# DAM10_Ethernet.net
KiCad netlist of a schematic drawn in Altium Designer
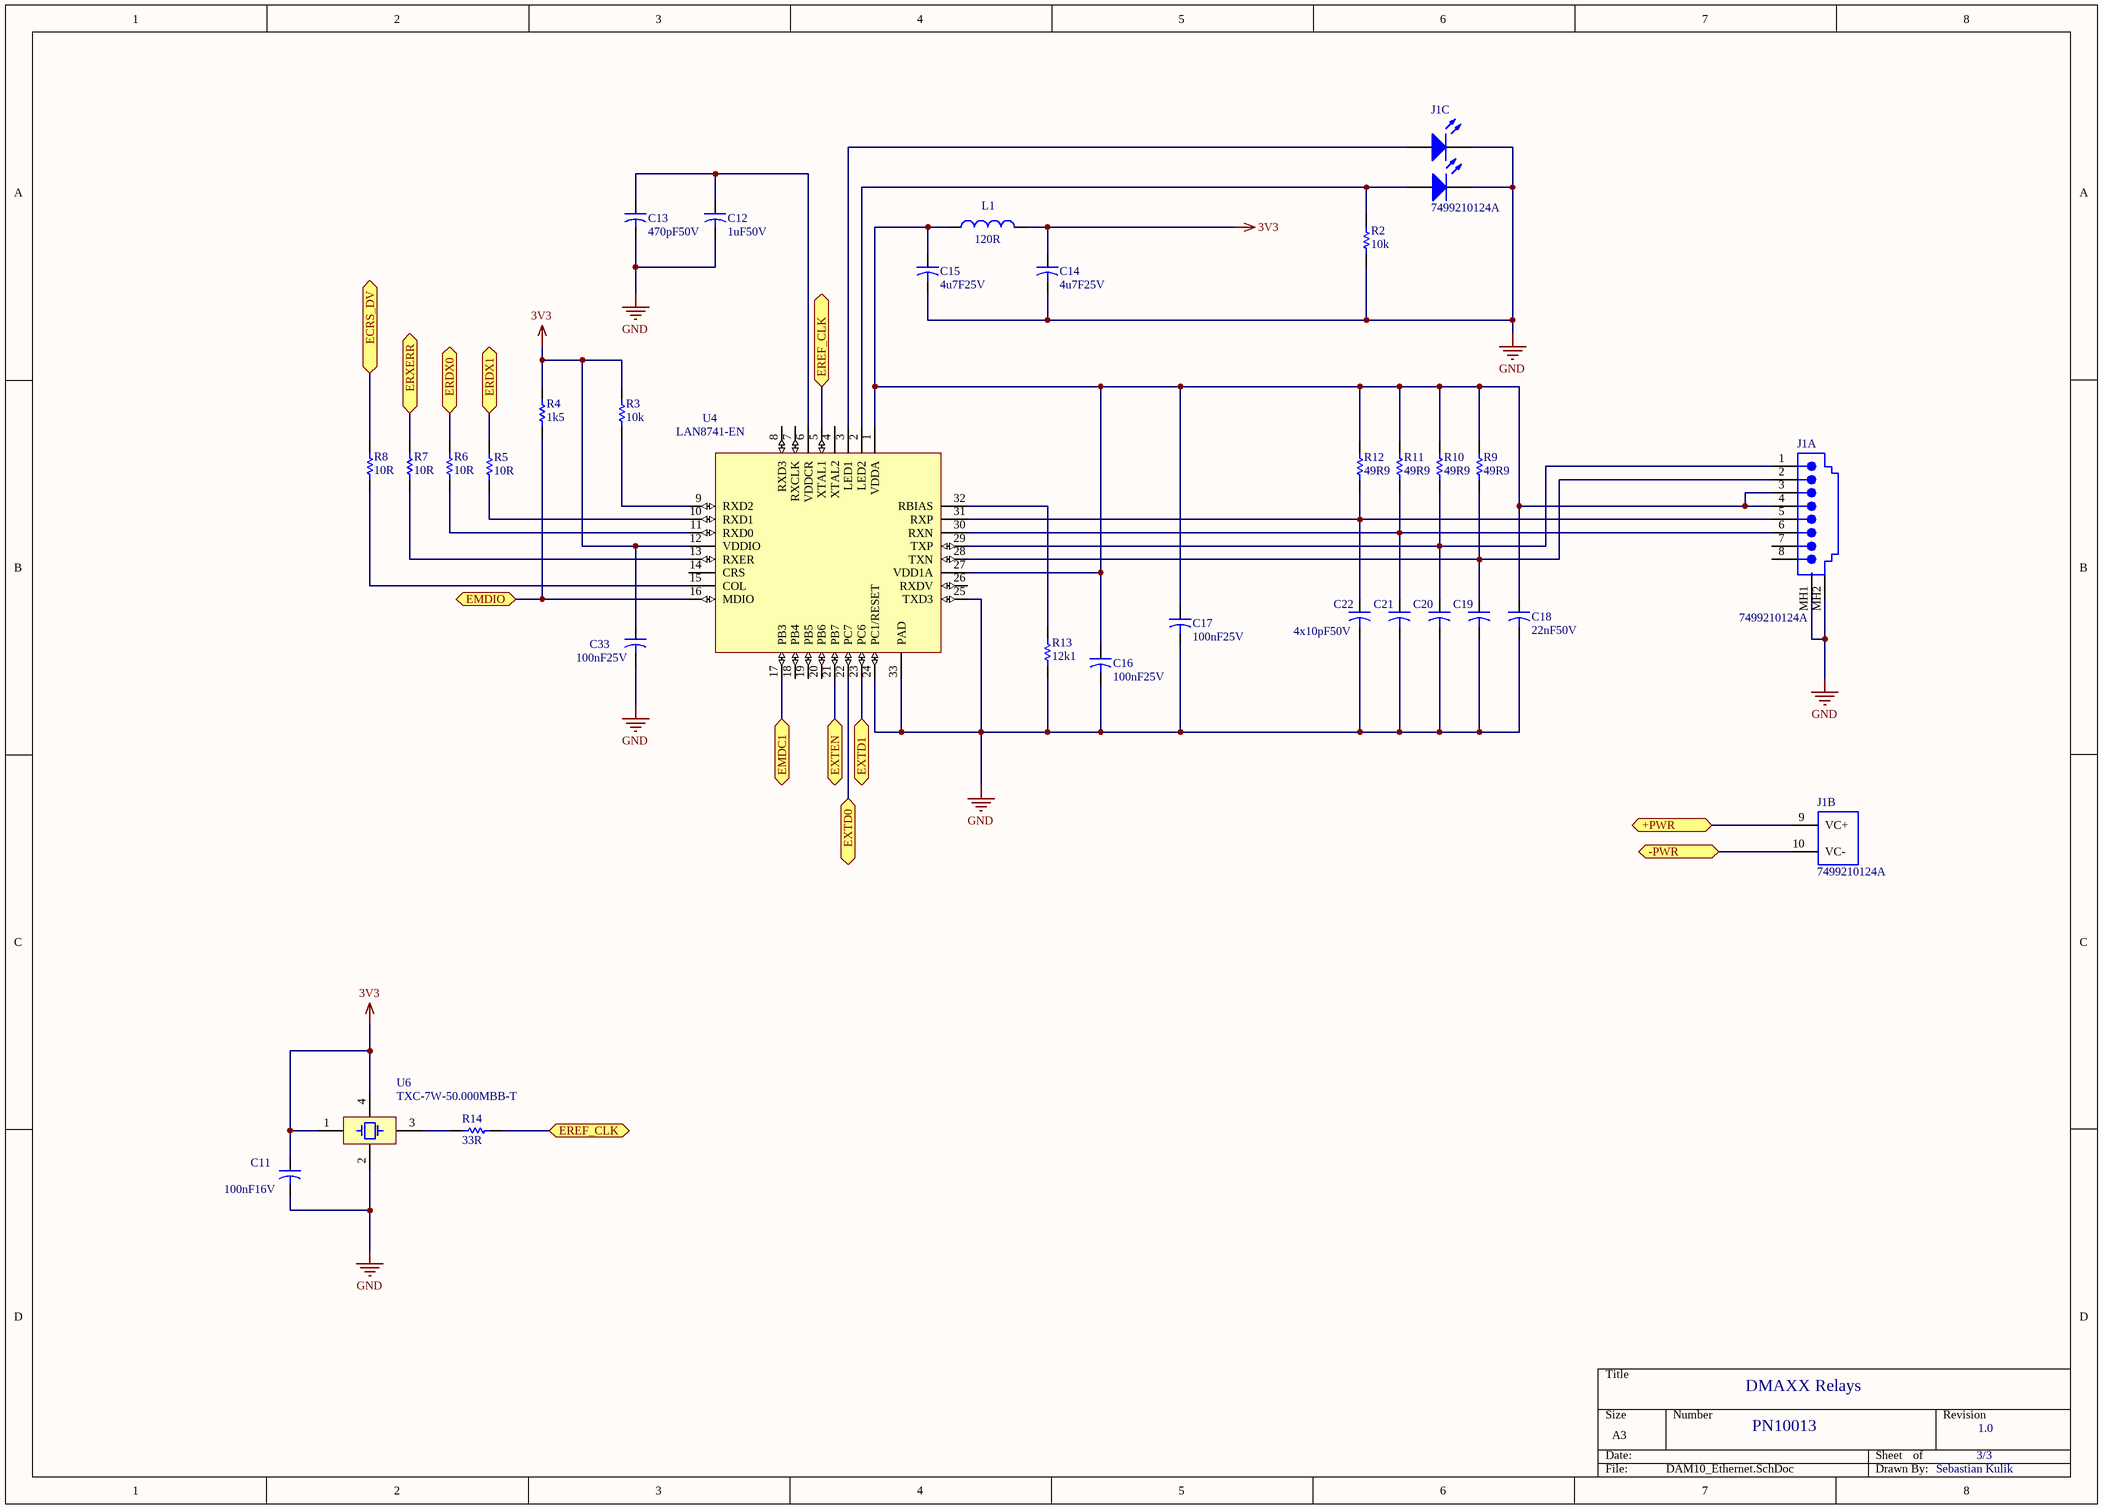
[diagram p0: DAM10_Ethernet.SchDoc]

(export (version "E")
  (design (tool "Eeschema 10.0.6"))
  (components
    (comp (ref "C11")
      (value "100nF16V")
      (footprint "C0402")
      (description "Capacitor")
      (fields
        (field (name "MANUFACTURER") "TDK")
        (field (name "Comment") "100nF16V_0402")
        (field (name "PUBLISHER") "Sebastian Kulik")
      )
      (libsource (lib "Capacitors") (part "100nF16V_0402"))
    )
    (comp (ref "C12")
      (value "1uF50V")
      (footprint "C0603")
      (description "C series, X5R, 10%")
      (fields
        (field (name "MANUFACTURER") "TDK")
        (field (name "Comment") "1uF50V_0603")
        (field (name "PUBLISHER") "Sebastian Kulik")
      )
      (libsource (lib "Capacitors") (part "1uF50V_0603"))
    )
    (comp (ref "C13")
      (value "470pF50V")
      (footprint "C0402")
      (description "AVX, 50V")
      (fields
        (field (name "MANUFACTURER") "AVX")
        (field (name "Comment") "470pF50V_0402")
        (field (name "PUBLISHER") "Sebastian Kulik")
      )
      (libsource (lib "Capacitors") (part "470pF50V_0402"))
    )
    (comp (ref "C14")
      (value "4u7F25V")
      (footprint "C0805")
      (description "TDK  C series, X7R, 10%, 25V")
      (fields
        (field (name "MANUFACTURER") "TDK")
        (field (name "Comment") "4u7F25V_0805")
        (field (name "PUBLISHER") "Sebastian Kulik")
      )
      (libsource (lib "Capacitors") (part "4u7F25V_0805"))
    )
    (comp (ref "C15")
      (value "4u7F25V")
      (footprint "C0805")
      (description "TDK  C series, X7R, 10%, 25V")
      (fields
        (field (name "MANUFACTURER") "TDK")
        (field (name "Comment") "4u7F25V_0805")
        (field (name "PUBLISHER") "Sebastian Kulik")
      )
      (libsource (lib "Capacitors") (part "4u7F25V_0805"))
    )
    (comp (ref "C16")
      (value "100nF25V")
      (footprint "C0402")
      (description "AVX, X5R, 10%, 25V")
      (fields
        (field (name "MANUFACTURER") "AVX")
        (field (name "Comment") "100nF25V_0402")
        (field (name "PUBLISHER") "Sebastian Kulik")
      )
      (libsource (lib "Capacitors") (part "100nF25V_0402"))
    )
    (comp (ref "C17")
      (value "100nF25V")
      (footprint "C0402")
      (description "AVX, X5R, 10%, 25V")
      (fields
        (field (name "MANUFACTURER") "AVX")
        (field (name "Comment") "100nF25V_0402")
        (field (name "PUBLISHER") "Sebastian Kulik")
      )
      (libsource (lib "Capacitors") (part "100nF25V_0402"))
    )
    (comp (ref "C18")
      (value "22nF50V")
      (footprint "C0603")
      (description "AVX ,  X7R, 5%, 50V")
      (fields
        (field (name "MANUFACTURER") "AVX")
        (field (name "Comment") "22nF50V_0603")
        (field (name "PUBLISHER") "Sebastian Kulik")
      )
      (libsource (lib "Capacitors") (part "22nF50V_0603"))
    )
    (comp (ref "C19")
      (value "10pF50V_0603")
      (footprint "C0603")
      (description "AVX ,  +-0.5pF, 50V")
      (fields (field (name "MANUFACTURER") "AVX") (field (name "PUBLISHER") "Sebastian Kulik"))
      (libsource (lib "Capacitors") (part "10pF50V_0603"))
    )
    (comp (ref "C20")
      (value "10pF50V_0603")
      (footprint "C0603")
      (description "AVX ,  +-0.5pF, 50V")
      (fields (field (name "MANUFACTURER") "AVX") (field (name "PUBLISHER") "Sebastian Kulik"))
      (libsource (lib "Capacitors") (part "10pF50V_0603"))
    )
    (comp (ref "C21")
      (value "10pF50V_0603")
      (footprint "C0603")
      (description "AVX ,  +-0.5pF, 50V")
      (fields (field (name "MANUFACTURER") "AVX") (field (name "PUBLISHER") "Sebastian Kulik"))
      (libsource (lib "Capacitors") (part "10pF50V_0603"))
    )
    (comp (ref "C22")
      (value "10pF50V_0603")
      (footprint "C0603")
      (description "AVX ,  +-0.5pF, 50V")
      (fields (field (name "MANUFACTURER") "AVX") (field (name "PUBLISHER") "Sebastian Kulik"))
      (libsource (lib "Capacitors") (part "10pF50V_0603"))
    )
    (comp (ref "C33")
      (value "100nF25V")
      (footprint "C0402")
      (description "AVX, X5R, 10%, 25V")
      (fields
        (field (name "MANUFACTURER") "AVX")
        (field (name "Comment") "100nF25V_0402")
        (field (name "PUBLISHER") "Sebastian Kulik")
      )
      (libsource (lib "Capacitors") (part "100nF25V_0402"))
    )
    (comp (ref "J1")
      (value "7499210124A")
      (footprint "7499210124A")
      (description "Modular Jack , Right Angle RJ-45, Low Profile")
      (fields (field (name "MANUFACTURER") "Wuerth Elektronik") (field (name "PUBLISHER") "Sebastian Kulik"))
      (libsource (lib "Connectors") (part "Ethernet, POE, WE7499210124A"))
    )
    (comp (ref "L1")
      (value "120R")
      (footprint "L0603")
      (description "Murata, Ferrit, 120Rx2A")
      (fields
        (field (name "MANUFACTURER") "Murata")
        (field (name "Comment") "120R4A_0603")
        (field (name "PUBLISHER") "Sebastian Kulik")
      )
      (libsource (lib "Passives") (part "120R4A_0603"))
    )
    (comp (ref "R2")
      (value "10k")
      (footprint "R0402")
      (description "Vishay CRCW series, 125mW, 1%")
      (fields
        (field (name "MANUFACTURER") "Vishay")
        (field (name "Comment") "10k_0402")
        (field (name "PUBLISHER") "Sebastian Kulik")
      )
      (libsource (lib "Resistors") (part "10k_0402"))
    )
    (comp (ref "R3")
      (value "10k")
      (footprint "R0402")
      (description "Vishay CRCW series, 125mW, 1%")
      (fields
        (field (name "MANUFACTURER") "Vishay")
        (field (name "Comment") "10k_0402")
        (field (name "PUBLISHER") "Sebastian Kulik")
      )
      (libsource (lib "Resistors") (part "10k_0402"))
    )
    (comp (ref "R4")
      (value "1k5")
      (footprint "R0402")
      (description "Vishay CRCW series, 125mW, 1%")
      (fields
        (field (name "MANUFACTURER") "Vishay")
        (field (name "Comment") "1k5_0402")
        (field (name "PUBLISHER") "Sebastian Kulik")
      )
      (libsource (lib "Resistors") (part "1k5_0402"))
    )
    (comp (ref "R5")
      (value "10R")
      (footprint "R0402")
      (description "Vishay CRCW series, 125mW, 1%")
      (fields
        (field (name "MANUFACTURER") "Vishay")
        (field (name "Comment") "10R_0402")
        (field (name "PUBLISHER") "Sebastian Kulik")
      )
      (libsource (lib "Resistors") (part "10R_0402"))
    )
    (comp (ref "R6")
      (value "10R")
      (footprint "R0402")
      (description "Vishay CRCW series, 125mW, 1%")
      (fields
        (field (name "MANUFACTURER") "Vishay")
        (field (name "Comment") "10R_0402")
        (field (name "PUBLISHER") "Sebastian Kulik")
      )
      (libsource (lib "Resistors") (part "10R_0402"))
    )
    (comp (ref "R7")
      (value "10R")
      (footprint "R0402")
      (description "Vishay CRCW series, 125mW, 1%")
      (fields
        (field (name "MANUFACTURER") "Vishay")
        (field (name "Comment") "10R_0402")
        (field (name "PUBLISHER") "Sebastian Kulik")
      )
      (libsource (lib "Resistors") (part "10R_0402"))
    )
    (comp (ref "R8")
      (value "10R")
      (footprint "R0402")
      (description "Vishay CRCW series, 125mW, 1%")
      (fields
        (field (name "MANUFACTURER") "Vishay")
        (field (name "Comment") "10R_0402")
        (field (name "PUBLISHER") "Sebastian Kulik")
      )
      (libsource (lib "Resistors") (part "10R_0402"))
    )
    (comp (ref "R9")
      (value "49R9")
      (footprint "R0402")
      (description "Vishay CRCW series, 63mW, 1%")
      (fields
        (field (name "MANUFACTURER") "Vishay")
        (field (name "Comment") "49R9_0402")
        (field (name "PUBLISHER") "Sebastian Kulik")
      )
      (libsource (lib "Resistors") (part "49R9_0402"))
    )
    (comp (ref "R10")
      (value "49R9")
      (footprint "R0402")
      (description "Vishay CRCW series, 63mW, 1%")
      (fields
        (field (name "MANUFACTURER") "Vishay")
        (field (name "Comment") "49R9_0402")
        (field (name "PUBLISHER") "Sebastian Kulik")
      )
      (libsource (lib "Resistors") (part "49R9_0402"))
    )
    (comp (ref "R11")
      (value "49R9")
      (footprint "R0402")
      (description "Vishay CRCW series, 63mW, 1%")
      (fields
        (field (name "MANUFACTURER") "Vishay")
        (field (name "Comment") "49R9_0402")
        (field (name "PUBLISHER") "Sebastian Kulik")
      )
      (libsource (lib "Resistors") (part "49R9_0402"))
    )
    (comp (ref "R12")
      (value "49R9")
      (footprint "R0402")
      (description "Vishay CRCW series, 63mW, 1%")
      (fields
        (field (name "MANUFACTURER") "Vishay")
        (field (name "Comment") "49R9_0402")
        (field (name "PUBLISHER") "Sebastian Kulik")
      )
      (libsource (lib "Resistors") (part "49R9_0402"))
    )
    (comp (ref "R13")
      (value "12k1")
      (footprint "R0603(1608)")
      (description "Vishay, CRCW series, 100mW, 1%")
      (fields
        (field (name "MANUFACTURER") "Vishay")
        (field (name "Comment") "12k1_0603")
        (field (name "PUBLISHER") "Sebastian Kulik")
      )
      (libsource (lib "Resistors") (part "12k1_0603"))
    )
    (comp (ref "R14")
      (value "33R")
      (footprint "R0402")
      (description "Vishay CRCW series, 63mW, 1%")
      (fields
        (field (name "MANUFACTURER") "Vishay")
        (field (name "Comment") "33R_0402")
        (field (name "PUBLISHER") "Sebastian Kulik")
      )
      (libsource (lib "Resistors") (part "33R_0402"))
    )
    (comp (ref "U4")
      (value "LAN8741-EN")
      (footprint "32M1-A_M")
      (description "Ethernet Phy")
      (fields (field (name "MANUFACTURER") "Microchip") (field (name "PUBLISHER") "Sebastian Kulik"))
      (libsource (lib "ICs") (part "LAN8741-EN"))
    )
    (comp (ref "U6")
      (value "TXC-7W-50.000MBB-T")
      (footprint "TXC_7W")
      (description "Crystal")
      (fields (field (name "MANUFACTURER") "TXC") (field (name "PUBLISHER") "Sebastian Kulik"))
      (libsource (lib "ICs") (part "TXC-7W-50.000MBB-T"))
    )
  )
  (nets
    (net (code "1") (name "/+PWR") (class "Default")
      (node (ref "J1") (pin "9") (pinfunction "VC+_9") (pintype "passive"))
    )
    (net (code "2") (name "/-PWR") (class "Default")
      (node (ref "J1") (pin "10") (pinfunction "VC-_10") (pintype "passive"))
    )
    (net (code "3") (name "/ECRS_DV") (class "Default")
      (node (ref "R8") (pin "2") (pinfunction "2_2") (pintype "passive"))
    )
    (net (code "4") (name "/EMDC1") (class "Default")
      (node (ref "U4") (pin "17") (pinfunction "PB3_17") (pintype "bidirectional"))
    )
    (net (code "5") (name "/EMDIO") (class "Default")
      (node (ref "R4") (pin "1") (pinfunction "1_1") (pintype "passive"))
      (node (ref "U4") (pin "16") (pinfunction "MDIO_16") (pintype "bidirectional"))
    )
    (net (code "6") (name "/ERDX0") (class "Default")
      (node (ref "R6") (pin "2") (pinfunction "2_2") (pintype "passive"))
    )
    (net (code "7") (name "/ERDX1") (class "Default")
      (node (ref "R5") (pin "1") (pinfunction "1_1") (pintype "passive"))
    )
    (net (code "8") (name "/EREF_CLK") (class "Default")
      (node (ref "R14") (pin "2") (pinfunction "2_2") (pintype "passive"))
      (node (ref "U4") (pin "5") (pinfunction "XTAL1_5") (pintype "bidirectional"))
    )
    (net (code "9") (name "/ERXERR") (class "Default")
      (node (ref "R7") (pin "2") (pinfunction "2_2") (pintype "passive"))
    )
    (net (code "10") (name "/EXTD0") (class "Default")
      (node (ref "U4") (pin "22") (pinfunction "PC7_22") (pintype "bidirectional"))
    )
    (net (code "11") (name "/EXTD1") (class "Default")
      (node (ref "U4") (pin "23") (pinfunction "PC6_23") (pintype "bidirectional"))
    )
    (net (code "12") (name "/EXTEN") (class "Default")
      (node (ref "U4") (pin "21") (pinfunction "PB7_21") (pintype "bidirectional"))
    )
    (net (code "13") (name "3V3") (class "Default")
      (node (ref "C11") (pin "1") (pinfunction "1_1") (pintype "passive"))
      (node (ref "C14") (pin "1") (pinfunction "1_1") (pintype "passive"))
      (node (ref "C33") (pin "1") (pinfunction "1_1") (pintype "passive"))
      (node (ref "L1") (pin "2") (pinfunction "2_2") (pintype "passive"))
      (node (ref "R3") (pin "2") (pinfunction "2_2") (pintype "passive"))
      (node (ref "R4") (pin "2") (pinfunction "2_2") (pintype "passive"))
      (node (ref "U4") (pin "12") (pinfunction "VDDIO_12") (pintype "passive"))
      (node (ref "U6") (pin "1") (pinfunction "E/D_1") (pintype "passive"))
      (node (ref "U6") (pin "4") (pinfunction "VCC_4") (pintype "passive"))
    )
    (net (code "14") (name "GND") (class "Default")
      (node (ref "C11") (pin "2") (pinfunction "2_2") (pintype "passive"))
      (node (ref "C12") (pin "2") (pinfunction "2_2") (pintype "passive"))
      (node (ref "C13") (pin "2") (pinfunction "2_2") (pintype "passive"))
      (node (ref "C14") (pin "2") (pinfunction "2_2") (pintype "passive"))
      (node (ref "C15") (pin "2") (pinfunction "2_2") (pintype "passive"))
      (node (ref "C16") (pin "2") (pinfunction "2_2") (pintype "passive"))
      (node (ref "C17") (pin "2") (pinfunction "2_2") (pintype "passive"))
      (node (ref "C18") (pin "2") (pinfunction "2_2") (pintype "passive"))
      (node (ref "C19") (pin "2") (pinfunction "2_2") (pintype "passive"))
      (node (ref "C20") (pin "2") (pinfunction "2_2") (pintype "passive"))
      (node (ref "C21") (pin "2") (pinfunction "2_2") (pintype "passive"))
      (node (ref "C22") (pin "2") (pinfunction "2_2") (pintype "passive"))
      (node (ref "C33") (pin "2") (pinfunction "2_2") (pintype "passive"))
      (node (ref "J1") (pin "11") (pinfunction "K_11") (pintype "passive"))
      (node (ref "J1") (pin "13") (pinfunction "K_13") (pintype "passive"))
      (node (ref "J1") (pin "MH1") (pinfunction "Shield_MH1") (pintype "passive"))
      (node (ref "J1") (pin "MH2") (pinfunction "Shield_MH2") (pintype "passive"))
      (node (ref "R13") (pin "1") (pinfunction "1_1") (pintype "passive"))
      (node (ref "R2") (pin "1") (pinfunction "1_1") (pintype "passive"))
      (node (ref "U4") (pin "24") (pinfunction "PC1/RESET_24") (pintype "bidirectional"))
      (node (ref "U4") (pin "25") (pinfunction "TXD3_25") (pintype "bidirectional"))
      (node (ref "U4") (pin "33") (pinfunction "PAD_33") (pintype "power_in"))
      (node (ref "U6") (pin "2") (pinfunction "GND_2") (pintype "passive"))
    )
    (net (code "15") (name "Net-(U4-COL)") (class "Default")
      (node (ref "R8") (pin "1") (pinfunction "1_1") (pintype "passive"))
      (node (ref "U4") (pin "15") (pinfunction "COL_15") (pintype "passive"))
    )
    (net (code "16") (name "Net-(U4-LED1)") (class "Default")
      (node (ref "J1") (pin "12") (pinfunction "A_12") (pintype "passive"))
      (node (ref "U4") (pin "3") (pinfunction "LED1_3") (pintype "power_in"))
    )
    (net (code "17") (name "Net-(U4-LED2)") (class "Default")
      (node (ref "J1") (pin "14") (pinfunction "A_14") (pintype "passive"))
      (node (ref "R2") (pin "2") (pinfunction "2_2") (pintype "passive"))
      (node (ref "U4") (pin "2") (pinfunction "LED2_2") (pintype "passive"))
    )
    (net (code "18") (name "Net-(U4-RBIAS)") (class "Default")
      (node (ref "R13") (pin "2") (pinfunction "2_2") (pintype "passive"))
      (node (ref "U4") (pin "32") (pinfunction "RBIAS_32") (pintype "power_in"))
    )
    (net (code "19") (name "Net-(U4-RXD0)") (class "Default")
      (node (ref "R6") (pin "1") (pinfunction "1_1") (pintype "passive"))
      (node (ref "U4") (pin "11") (pinfunction "RXD0_11") (pintype "bidirectional"))
    )
    (net (code "20") (name "Net-(U4-RXD1)") (class "Default")
      (node (ref "R5") (pin "2") (pinfunction "2_2") (pintype "passive"))
      (node (ref "U4") (pin "10") (pinfunction "RXD1_10") (pintype "bidirectional"))
    )
    (net (code "21") (name "Net-(U4-RXD2)") (class "Default")
      (node (ref "R3") (pin "1") (pinfunction "1_1") (pintype "passive"))
      (node (ref "U4") (pin "9") (pinfunction "RXD2_9") (pintype "bidirectional"))
    )
    (net (code "22") (name "Net-(U4-RXER)") (class "Default")
      (node (ref "R7") (pin "1") (pinfunction "1_1") (pintype "passive"))
      (node (ref "U4") (pin "13") (pinfunction "RXER_13") (pintype "bidirectional"))
    )
    (net (code "23") (name "Net-(U4-RXN)") (class "Default")
      (node (ref "C21") (pin "1") (pinfunction "1_1") (pintype "passive"))
      (node (ref "J1") (pin "6") (pinfunction "6_6") (pintype "passive"))
      (node (ref "R11") (pin "1") (pinfunction "1_1") (pintype "passive"))
      (node (ref "U4") (pin "30") (pinfunction "RXN_30") (pintype "passive"))
    )
    (net (code "24") (name "Net-(U4-RXP)") (class "Default")
      (node (ref "C22") (pin "1") (pinfunction "1_1") (pintype "passive"))
      (node (ref "J1") (pin "5") (pinfunction "5_5") (pintype "passive"))
      (node (ref "R12") (pin "1") (pinfunction "1_1") (pintype "passive"))
      (node (ref "U4") (pin "31") (pinfunction "RXP_31") (pintype "passive"))
    )
    (net (code "25") (name "Net-(U4-TXN)") (class "Default")
      (node (ref "C19") (pin "1") (pinfunction "1_1") (pintype "passive"))
      (node (ref "J1") (pin "2") (pinfunction "2_2") (pintype "passive"))
      (node (ref "R9") (pin "1") (pinfunction "1_1") (pintype "passive"))
      (node (ref "U4") (pin "28") (pinfunction "TXN_28") (pintype "bidirectional"))
    )
    (net (code "26") (name "Net-(U4-TXP)") (class "Default")
      (node (ref "C20") (pin "1") (pinfunction "1_1") (pintype "passive"))
      (node (ref "J1") (pin "1") (pinfunction "1_1") (pintype "passive"))
      (node (ref "R10") (pin "1") (pinfunction "1_1") (pintype "passive"))
      (node (ref "U4") (pin "29") (pinfunction "TXP_29") (pintype "bidirectional"))
    )
    (net (code "27") (name "Net-(U4-VDD1A)") (class "Default")
      (node (ref "C15") (pin "1") (pinfunction "1_1") (pintype "passive"))
      (node (ref "C16") (pin "1") (pinfunction "1_1") (pintype "passive"))
      (node (ref "C17") (pin "1") (pinfunction "1_1") (pintype "passive"))
      (node (ref "C18") (pin "1") (pinfunction "1_1") (pintype "passive"))
      (node (ref "J1") (pin "3") (pinfunction "3_3") (pintype "passive"))
      (node (ref "J1") (pin "4") (pinfunction "4_4") (pintype "passive"))
      (node (ref "L1") (pin "1") (pinfunction "1_1") (pintype "passive"))
      (node (ref "R10") (pin "2") (pinfunction "2_2") (pintype "passive"))
      (node (ref "R11") (pin "2") (pinfunction "2_2") (pintype "passive"))
      (node (ref "R12") (pin "2") (pinfunction "2_2") (pintype "passive"))
      (node (ref "R9") (pin "2") (pinfunction "2_2") (pintype "passive"))
      (node (ref "U4") (pin "1") (pinfunction "VDDA_1") (pintype "passive"))
      (node (ref "U4") (pin "27") (pinfunction "VDD1A_27") (pintype "passive"))
    )
    (net (code "28") (name "Net-(U4-VDDCR)") (class "Default")
      (node (ref "C12") (pin "1") (pinfunction "1_1") (pintype "passive"))
      (node (ref "C13") (pin "1") (pinfunction "1_1") (pintype "passive"))
      (node (ref "U4") (pin "6") (pinfunction "VDDCR_6") (pintype "passive"))
    )
    (net (code "29") (name "Net-(U6-OSC2)") (class "Default")
      (node (ref "R14") (pin "1") (pinfunction "1_1") (pintype "passive"))
      (node (ref "U6") (pin "3") (pinfunction "OSC2_3") (pintype "passive"))
    )
    (net (code "30") (name "unconnected-(J1-Pad7)") (class "Default")
      (node (ref "J1") (pin "7") (pinfunction "7_7") (pintype "passive"))
    )
    (net (code "31") (name "unconnected-(J1-Pad8)") (class "Default")
      (node (ref "J1") (pin "8") (pinfunction "8_8") (pintype "passive"))
    )
    (net (code "32") (name "unconnected-(U4-CRS-Pad14)") (class "Default")
      (node (ref "U4") (pin "14") (pinfunction "CRS_14") (pintype "passive"))
    )
    (net (code "33") (name "unconnected-(U4-PB4-Pad18)") (class "Default")
      (node (ref "U4") (pin "18") (pinfunction "PB4_18") (pintype "bidirectional"))
    )
    (net (code "34") (name "unconnected-(U4-PB5-Pad19)") (class "Default")
      (node (ref "U4") (pin "19") (pinfunction "PB5_19") (pintype "bidirectional"))
    )
    (net (code "35") (name "unconnected-(U4-PB6-Pad20)") (class "Default")
      (node (ref "U4") (pin "20") (pinfunction "PB6_20") (pintype "bidirectional"))
    )
    (net (code "36") (name "unconnected-(U4-RXCLK-Pad7)") (class "Default")
      (node (ref "U4") (pin "7") (pinfunction "RXCLK_7") (pintype "bidirectional"))
    )
    (net (code "37") (name "unconnected-(U4-RXD3-Pad8)") (class "Default")
      (node (ref "U4") (pin "8") (pinfunction "RXD3_8") (pintype "bidirectional"))
    )
    (net (code "38") (name "unconnected-(U4-RXDV-Pad26)") (class "Default")
      (node (ref "U4") (pin "26") (pinfunction "RXDV_26") (pintype "bidirectional"))
    )
    (net (code "39") (name "unconnected-(U4-XTAL2-Pad4)") (class "Default")
      (node (ref "U4") (pin "4") (pinfunction "XTAL2_4") (pintype "power_in"))
    )
  )
)
